# AC-DC_Convertor_Rev2.net
KiCad netlist of a schematic drawn in EAGLE
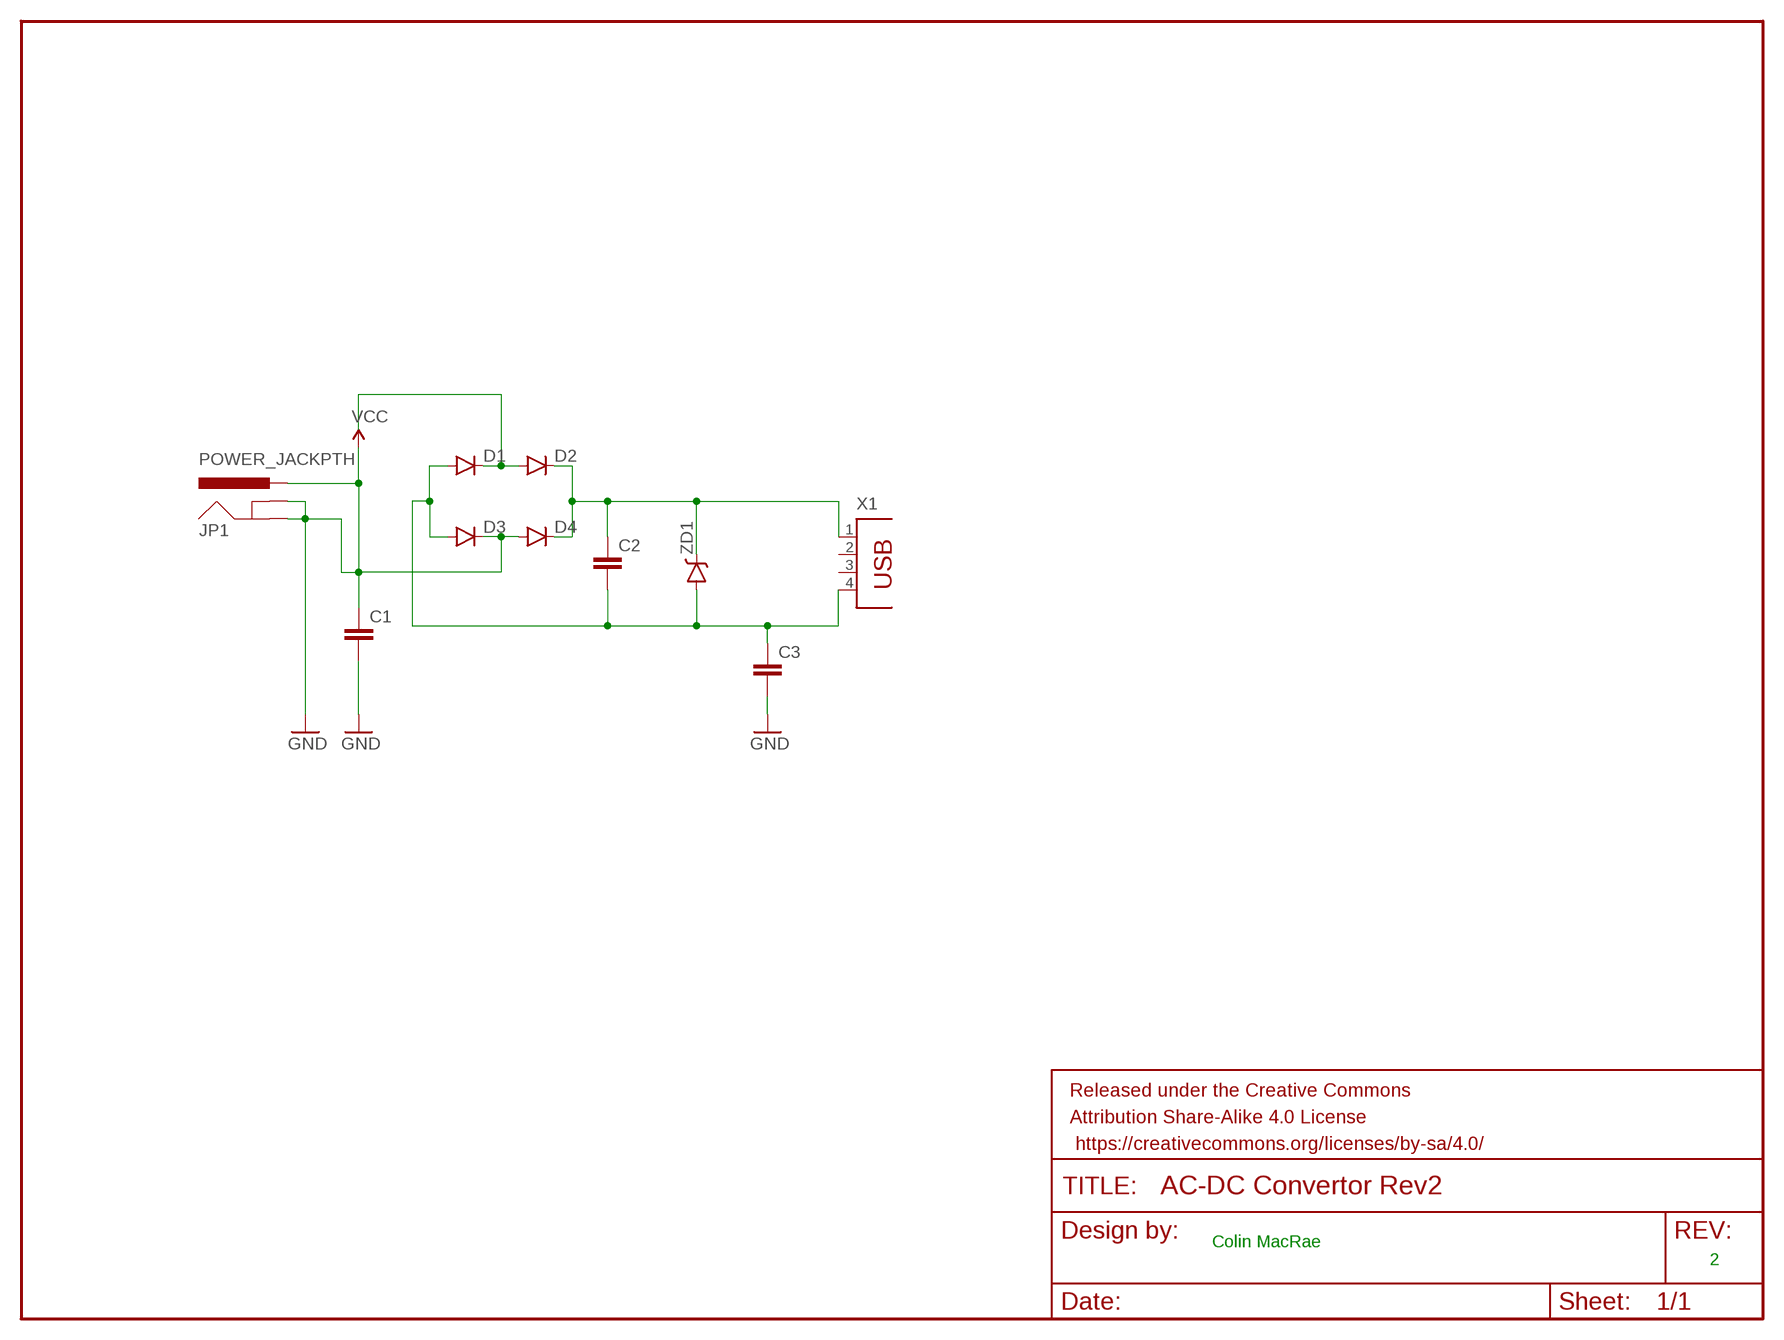
[diagram p0: schematic, sheet 1]

(export (version "E")
  (design (tool "Eeschema 10.0.6"))
  (components
    (comp (ref "C1")
      (value "CAPEZ")
      (footprint "eagle-import:CAP-PTH-SMALLEZ")
      (libsource (lib "eagle-import") (part "CAPEZ"))
    )
    (comp (ref "C2")
      (value "CAPEZ")
      (footprint "eagle-import:CAP-PTH-SMALLEZ")
      (libsource (lib "eagle-import") (part "CAPEZ"))
    )
    (comp (ref "C3")
      (value "CAPEZ")
      (footprint "eagle-import:CAP-PTH-SMALLEZ")
      (libsource (lib "eagle-import") (part "CAPEZ"))
    )
    (comp (ref "D1")
      (value "DIODEKIT2")
      (footprint "eagle-import:DIODE-1N4001-KIT")
      (libsource (lib "eagle-import") (part "DIODEKIT2"))
    )
    (comp (ref "D2")
      (value "DIODEKIT2")
      (footprint "eagle-import:DIODE-1N4001-KIT")
      (libsource (lib "eagle-import") (part "DIODEKIT2"))
    )
    (comp (ref "D3")
      (value "DIODEKIT2")
      (footprint "eagle-import:DIODE-1N4001-KIT")
      (libsource (lib "eagle-import") (part "DIODEKIT2"))
    )
    (comp (ref "D4")
      (value "DIODEKIT2")
      (footprint "eagle-import:DIODE-1N4001-KIT")
      (libsource (lib "eagle-import") (part "DIODEKIT2"))
    )
    (comp (ref "FRAME1")
      (value "FRAME-LETTER")
      (footprint "eagle-import:CREATIVE_COMMONS")
      (libsource (lib "eagle-import") (part "FRAME-LETTER"))
    )
    (comp (ref "JP1")
      (value "POWER_JACKPTH")
      (footprint "eagle-import:POWER_JACK_PTH")
      (libsource (lib "eagle-import") (part "POWER_JACKPTH"))
    )
    (comp (ref "X1")
      (value "PN87520")
      (footprint "eagle-import:PN87520")
      (libsource (lib "eagle-import") (part "PN87520"))
    )
    (comp (ref "ZD1")
      (value "V-REFERENCESMD")
      (footprint "eagle-import:SOT23-3")
      (libsource (lib "eagle-import") (part "V-REFERENCESMD"))
    )
  )
  (nets
    (net (code "1") (name "GND") (class "Default")
      (node (ref "C1") (pin "1") (pinfunction "1_1") (pintype "passive"))
      (node (ref "C1") (pin "2") (pinfunction "2_2") (pintype "passive"))
      (node (ref "C3") (pin "2") (pinfunction "2_2") (pintype "passive"))
      (node (ref "D3") (pin "C") (pinfunction "C_C") (pintype "passive"))
      (node (ref "D4") (pin "A") (pinfunction "A_A") (pintype "passive"))
      (node (ref "JP1") (pin "GND") (pinfunction "GND_GND") (pintype "bidirectional"))
      (node (ref "JP1") (pin "GNDBREAK") (pinfunction "GNDBREAK_GNDBREAK") (pintype "bidirectional"))
      (node (ref "JP1") (pin "PWR") (pinfunction "PWR_PWR") (pintype "bidirectional"))
    )
    (net (code "2") (name "Net-(D1-PadC)") (class "Default")
      (node (ref "D1") (pin "C") (pinfunction "C_C") (pintype "passive"))
      (node (ref "D2") (pin "A") (pinfunction "A_A") (pintype "passive"))
    )
    (net (code "3") (name "Net-(ZD1-A)") (class "Default")
      (node (ref "C2") (pin "2") (pinfunction "2_2") (pintype "passive"))
      (node (ref "C3") (pin "1") (pinfunction "1_1") (pintype "passive"))
      (node (ref "D1") (pin "A") (pinfunction "A_A") (pintype "passive"))
      (node (ref "D3") (pin "A") (pinfunction "A_A") (pintype "passive"))
      (node (ref "X1") (pin "4") (pinfunction "4_4") (pintype "passive"))
      (node (ref "ZD1") (pin "2") (pinfunction "A_2") (pintype "passive"))
    )
    (net (code "4") (name "Net-(ZD1-C)") (class "Default")
      (node (ref "C2") (pin "1") (pinfunction "1_1") (pintype "passive"))
      (node (ref "D2") (pin "C") (pinfunction "C_C") (pintype "passive"))
      (node (ref "D4") (pin "C") (pinfunction "C_C") (pintype "passive"))
      (node (ref "X1") (pin "1") (pinfunction "1_1") (pintype "passive"))
      (node (ref "ZD1") (pin "1") (pinfunction "C_1") (pintype "passive"))
    )
    (net (code "5") (name "unconnected-(X1-Pad2)") (class "Default")
      (node (ref "X1") (pin "2") (pinfunction "2_2") (pintype "passive"))
    )
    (net (code "6") (name "unconnected-(X1-Pad3)") (class "Default")
      (node (ref "X1") (pin "3") (pinfunction "3_3") (pintype "passive"))
    )
  )
)
